# gk_midi_board.net
KiCad netlist of a schematic drawn in EAGLE
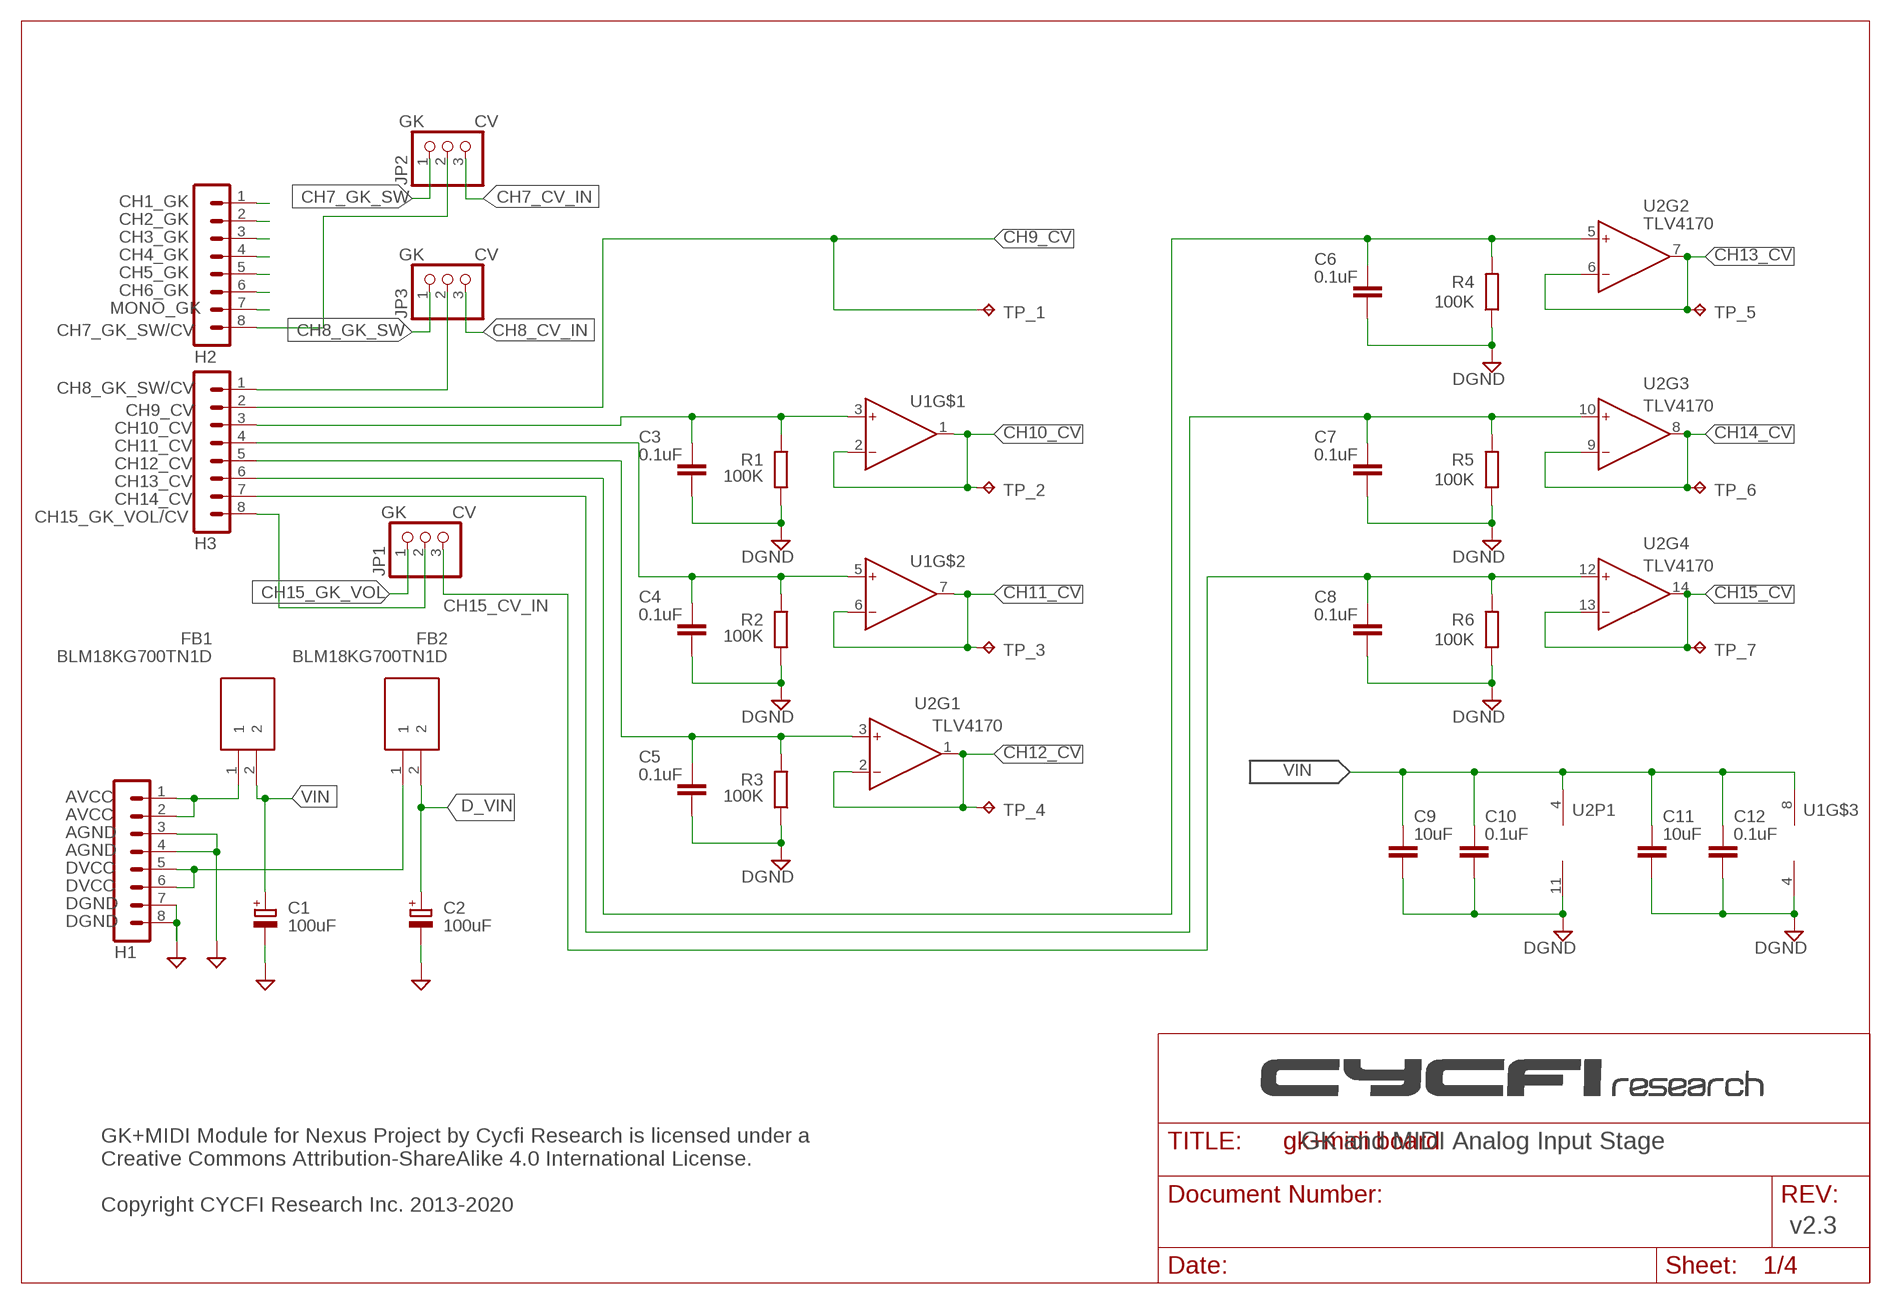
[diagram p0: schematic, sheet 1]
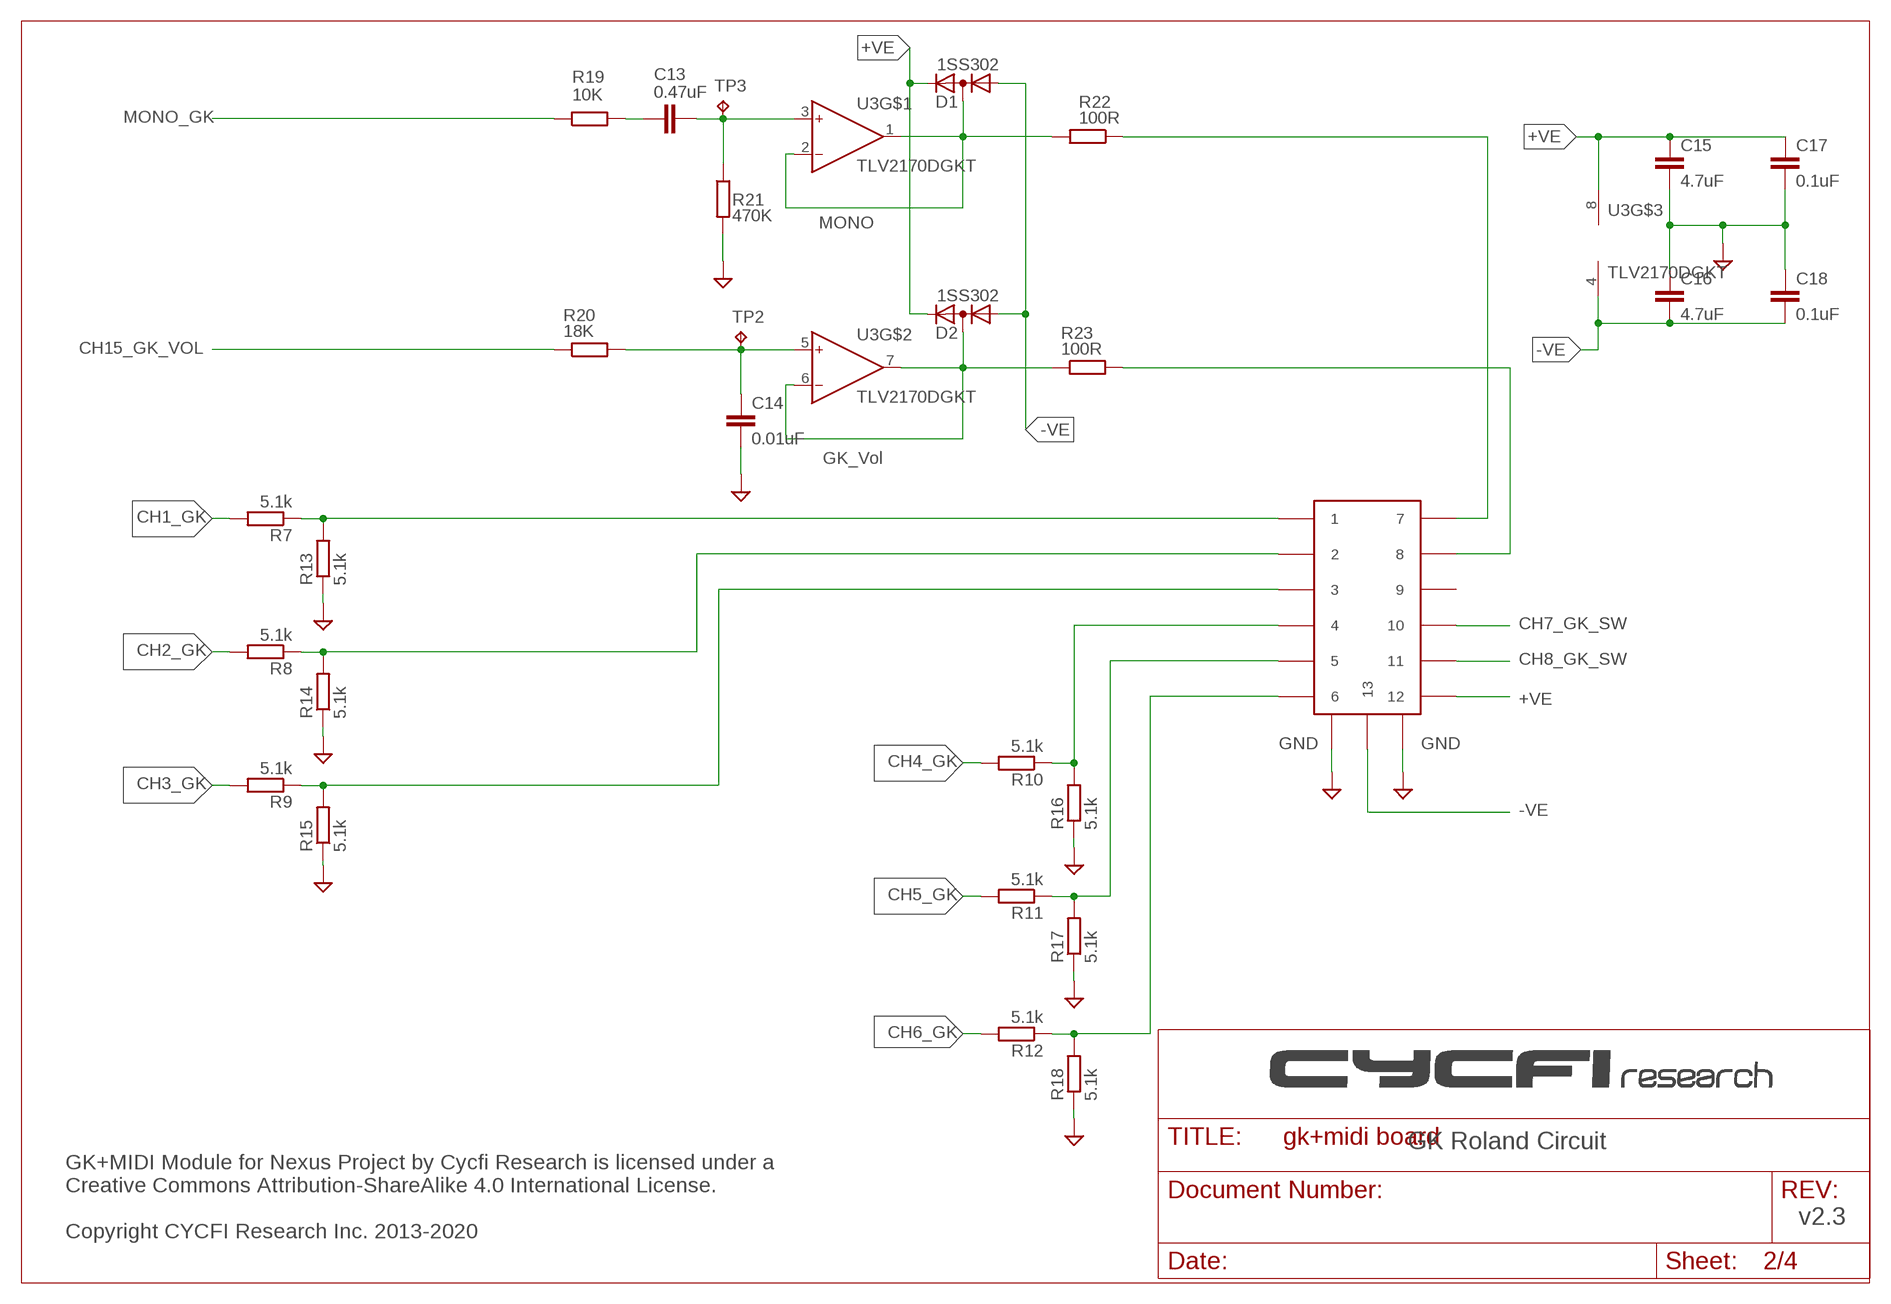
[diagram p1: schematic, sheet 2]
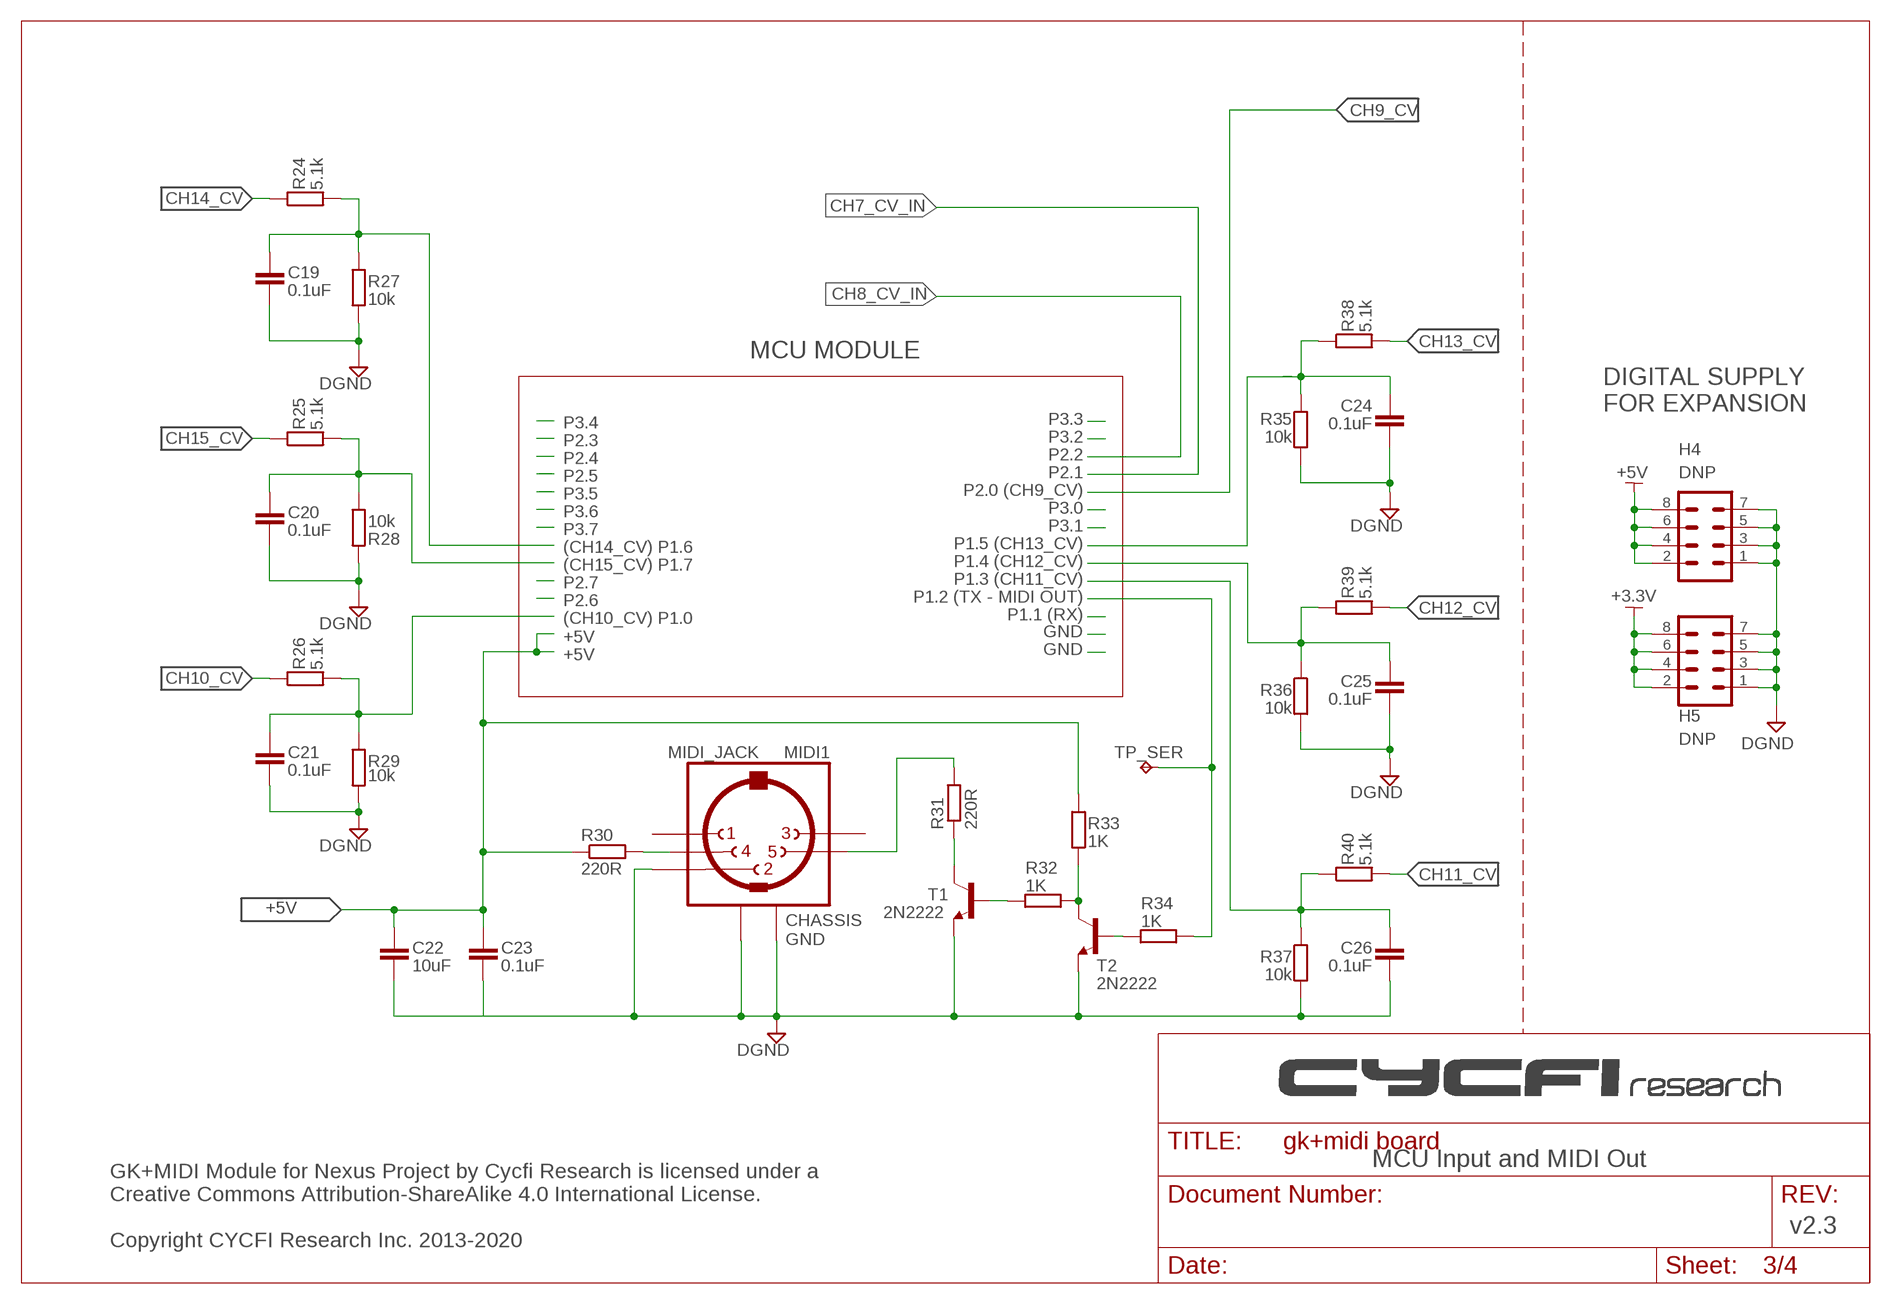
[diagram p2: schematic, sheet 3]
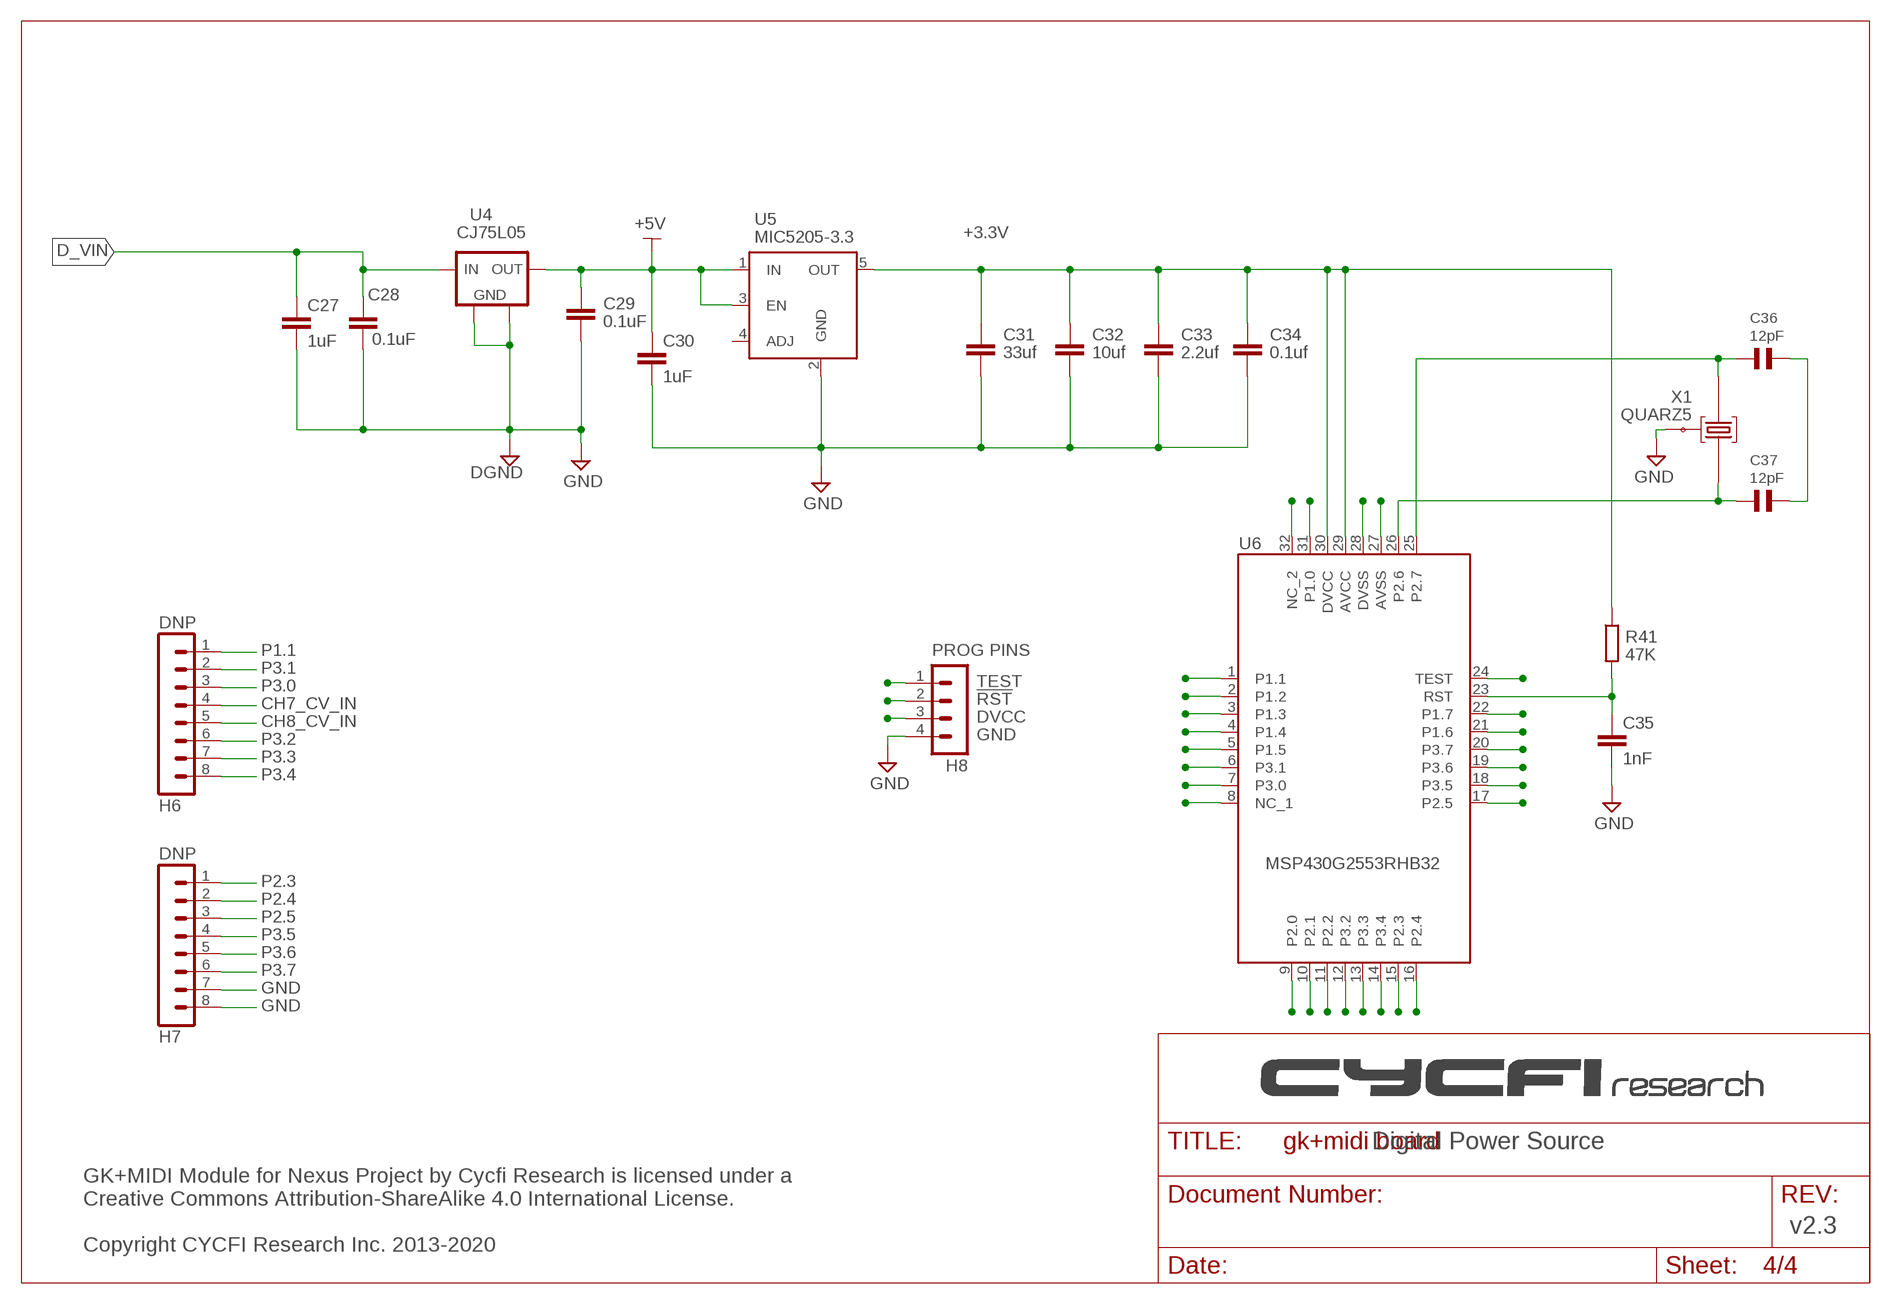
[diagram p3: schematic, sheet 4]

(export (version "E")
  (design (tool "Eeschema 10.0.6"))
  (components
    (comp (ref "13P-CN1")
      (value "13P-MIDI")
      (footprint "eagle-import:13P-MIDI")
      (libsource (lib "eagle-import") (part "13P-MIDI"))
    )
    (comp (ref "C13")
      (value "0.47uF")
      (footprint "eagle-import:C0603")
      (libsource (lib "eagle-import") (part "C-EUC0603"))
    )
    (comp (ref "C14")
      (value "0.01uF")
      (footprint "eagle-import:C0402")
      (libsource (lib "eagle-import") (part "C-EUC0402"))
    )
    (comp (ref "C15")
      (value "4.7uF")
      (footprint "eagle-import:C0603")
      (libsource (lib "eagle-import") (part "C-EUC0603"))
    )
    (comp (ref "C16")
      (value "4.7uF")
      (footprint "eagle-import:C0603")
      (libsource (lib "eagle-import") (part "C-EUC0603"))
    )
    (comp (ref "C17")
      (value "0.1uF")
      (footprint "eagle-import:C0402")
      (libsource (lib "eagle-import") (part "C-EUC0402"))
    )
    (comp (ref "C18")
      (value "0.1uF")
      (footprint "eagle-import:C0402")
      (libsource (lib "eagle-import") (part "C-EUC0402"))
    )
    (comp (ref "D1")
      (value "1SS302")
      (footprint "eagle-import:SC70-3")
      (libsource (lib "eagle-import") (part "1SS302"))
    )
    (comp (ref "D2")
      (value "1SS302")
      (footprint "eagle-import:SC70-3")
      (libsource (lib "eagle-import") (part "1SS302"))
    )
    (comp (ref "R7")
      (value "5.1k")
      (footprint "eagle-import:R0402")
      (libsource (lib "eagle-import") (part "R-EU_R0402"))
    )
    (comp (ref "R8")
      (value "5.1k")
      (footprint "eagle-import:R0402")
      (libsource (lib "eagle-import") (part "R-EU_R0402"))
    )
    (comp (ref "R9")
      (value "5.1k")
      (footprint "eagle-import:R0402")
      (libsource (lib "eagle-import") (part "R-EU_R0402"))
    )
    (comp (ref "R10")
      (value "5.1k")
      (footprint "eagle-import:R0402")
      (libsource (lib "eagle-import") (part "R-EU_R0402"))
    )
    (comp (ref "R11")
      (value "5.1k")
      (footprint "eagle-import:R0402")
      (libsource (lib "eagle-import") (part "R-EU_R0402"))
    )
    (comp (ref "R12")
      (value "5.1k")
      (footprint "eagle-import:R0402")
      (libsource (lib "eagle-import") (part "R-EU_R0402"))
    )
    (comp (ref "R13")
      (value "5.1k")
      (footprint "eagle-import:R0402")
      (libsource (lib "eagle-import") (part "R-EU_R0402"))
    )
    (comp (ref "R14")
      (value "5.1k")
      (footprint "eagle-import:R0402")
      (libsource (lib "eagle-import") (part "R-EU_R0402"))
    )
    (comp (ref "R15")
      (value "5.1k")
      (footprint "eagle-import:R0402")
      (libsource (lib "eagle-import") (part "R-EU_R0402"))
    )
    (comp (ref "R16")
      (value "5.1k")
      (footprint "eagle-import:R0402")
      (libsource (lib "eagle-import") (part "R-EU_R0402"))
    )
    (comp (ref "R17")
      (value "5.1k")
      (footprint "eagle-import:R0402")
      (libsource (lib "eagle-import") (part "R-EU_R0402"))
    )
    (comp (ref "R18")
      (value "5.1k")
      (footprint "eagle-import:R0402")
      (libsource (lib "eagle-import") (part "R-EU_R0402"))
    )
    (comp (ref "R19")
      (value "10K")
      (footprint "eagle-import:R0402")
      (libsource (lib "eagle-import") (part "R-EU_R0402"))
    )
    (comp (ref "R20")
      (value "18K")
      (footprint "eagle-import:R0402")
      (libsource (lib "eagle-import") (part "R-EU_R0402"))
    )
    (comp (ref "R21")
      (value "470K")
      (footprint "eagle-import:R0402")
      (libsource (lib "eagle-import") (part "R-EU_R0402"))
    )
    (comp (ref "R22")
      (value "100R")
      (footprint "eagle-import:R0402")
      (libsource (lib "eagle-import") (part "R-EU_R0402"))
    )
    (comp (ref "R23")
      (value "100R")
      (footprint "eagle-import:R0402")
      (libsource (lib "eagle-import") (part "R-EU_R0402"))
    )
    (comp (ref "TP2")
      (value "TPB1,27")
      (footprint "eagle-import:B1,27")
      (libsource (lib "eagle-import") (part "TPB1,27"))
    )
    (comp (ref "TP3")
      (value "TPB1,27")
      (footprint "eagle-import:B1,27")
      (libsource (lib "eagle-import") (part "TPB1,27"))
    )
    (comp (ref "U3")
      (value "TLV2170DGKT")
      (footprint "eagle-import:MSOP8")
      (libsource (lib "eagle-import") (part "TLV2170DGKT"))
    )
    (comp (ref "C1")
      (value "100uF")
      (footprint "eagle-import:153CLV-0505")
      (libsource (lib "eagle-import") (part "CPOL-EU153CLV-0505"))
    )
    (comp (ref "C2")
      (value "100uF")
      (footprint "eagle-import:153CLV-0505")
      (libsource (lib "eagle-import") (part "CPOL-EU153CLV-0505"))
    )
    (comp (ref "C3")
      (value "0.1uF")
      (footprint "eagle-import:C0603")
      (libsource (lib "eagle-import") (part "C-EUC0603"))
    )
    (comp (ref "C4")
      (value "0.1uF")
      (footprint "eagle-import:C0603")
      (libsource (lib "eagle-import") (part "C-EUC0603"))
    )
    (comp (ref "C5")
      (value "0.1uF")
      (footprint "eagle-import:C0603")
      (libsource (lib "eagle-import") (part "C-EUC0603"))
    )
    (comp (ref "C6")
      (value "0.1uF")
      (footprint "eagle-import:C0603")
      (libsource (lib "eagle-import") (part "C-EUC0603"))
    )
    (comp (ref "C7")
      (value "0.1uF")
      (footprint "eagle-import:C0603")
      (libsource (lib "eagle-import") (part "C-EUC0603"))
    )
    (comp (ref "C8")
      (value "0.1uF")
      (footprint "eagle-import:C0603")
      (libsource (lib "eagle-import") (part "C-EUC0603"))
    )
    (comp (ref "C9")
      (value "10uF")
      (footprint "eagle-import:C0805")
      (libsource (lib "eagle-import") (part "C-EUC0805"))
    )
    (comp (ref "C10")
      (value "0.1uF")
      (footprint "eagle-import:C0603")
      (libsource (lib "eagle-import") (part "C-EUC0603"))
    )
    (comp (ref "C11")
      (value "10uF")
      (footprint "eagle-import:C0805")
      (libsource (lib "eagle-import") (part "C-EUC0805"))
    )
    (comp (ref "C12")
      (value "0.1uF")
      (footprint "eagle-import:C0603")
      (libsource (lib "eagle-import") (part "C-EUC0603"))
    )
    (comp (ref "FB1")
      (value "BLM18KG700TN1D")
      (footprint "eagle-import:BEADC1608X75N")
      (fields (field (name "MOUSER_PART_NUMBER") "81-BLM18KG700TN1D"))
      (libsource (lib "eagle-import") (part "BLM18KG700TN1D"))
    )
    (comp (ref "FB2")
      (value "BLM18KG700TN1D")
      (footprint "eagle-import:BEADC1608X75N")
      (description "BLM18_N1D Series EMI Suppression Filter 70+/-25% at 100MHz 3.5A @85")
      (fields
        (field (name "MOUSER_PART_NUMBER") "81-BLM18KG700TN1D")
        (field (name "HEIGHT") "0.75mm")
        (field (name "MANUFACTURER_NAME") "Murata Electronics")
        (field (name "MANUFACTURER_PART_NUMBER") "BLM18KG700TN1D")
        (field (name "MOUSER_PART_NUMBER_1") "81-BLM18KG700TN1D")
        (field (name "MOUSER_PRICE-STOCK") "https://www.mouser.com/Search/Refine.aspx?Keyword=81-BLM18KG700TN1D")
      )
      (libsource (lib "eagle-import") (part "BLM18KG700TN1D"))
    )
    (comp (ref "H1")
      (value "MA08-1")
      (footprint "eagle-import:MA08-1")
      (libsource (lib "eagle-import") (part "MA08-1"))
    )
    (comp (ref "H2")
      (value "MA08-1")
      (footprint "eagle-import:MA08-1")
      (libsource (lib "eagle-import") (part "MA08-1"))
    )
    (comp (ref "H3")
      (value "MA08-1")
      (footprint "eagle-import:MA08-1")
      (libsource (lib "eagle-import") (part "MA08-1"))
    )
    (comp (ref "JP1")
      (value "PINHD-1X03_2.00")
      (footprint "eagle-import:1X03M")
      (libsource (lib "eagle-import") (part "PINHD-1X03_2.00"))
    )
    (comp (ref "JP2")
      (value "PINHD-1X03_2.00")
      (footprint "eagle-import:1X03M")
      (libsource (lib "eagle-import") (part "PINHD-1X03_2.00"))
    )
    (comp (ref "JP3")
      (value "PINHD-1X03_2.00")
      (footprint "eagle-import:1X03M")
      (libsource (lib "eagle-import") (part "PINHD-1X03_2.00"))
    )
    (comp (ref "R1")
      (value "100K")
      (footprint "eagle-import:R0402")
      (libsource (lib "eagle-import") (part "R-EU_R0402"))
    )
    (comp (ref "R2")
      (value "100K")
      (footprint "eagle-import:R0402")
      (libsource (lib "eagle-import") (part "R-EU_R0402"))
    )
    (comp (ref "R3")
      (value "100K")
      (footprint "eagle-import:R0402")
      (libsource (lib "eagle-import") (part "R-EU_R0402"))
    )
    (comp (ref "R4")
      (value "100K")
      (footprint "eagle-import:R0402")
      (libsource (lib "eagle-import") (part "R-EU_R0402"))
    )
    (comp (ref "R5")
      (value "100K")
      (footprint "eagle-import:R0402")
      (libsource (lib "eagle-import") (part "R-EU_R0402"))
    )
    (comp (ref "R6")
      (value "100K")
      (footprint "eagle-import:R0402")
      (libsource (lib "eagle-import") (part "R-EU_R0402"))
    )
    (comp (ref "TP_1")
      (value "TPB1,27")
      (footprint "eagle-import:B1,27")
      (libsource (lib "eagle-import") (part "TPB1,27"))
    )
    (comp (ref "TP_2")
      (value "TPB1,27")
      (footprint "eagle-import:B1,27")
      (libsource (lib "eagle-import") (part "TPB1,27"))
    )
    (comp (ref "TP_3")
      (value "TPB1,27")
      (footprint "eagle-import:B1,27")
      (libsource (lib "eagle-import") (part "TPB1,27"))
    )
    (comp (ref "TP_4")
      (value "TPB1,27")
      (footprint "eagle-import:B1,27")
      (libsource (lib "eagle-import") (part "TPB1,27"))
    )
    (comp (ref "TP_5")
      (value "TPB1,27")
      (footprint "eagle-import:B1,27")
      (libsource (lib "eagle-import") (part "TPB1,27"))
    )
    (comp (ref "TP_6")
      (value "TPB1,27")
      (footprint "eagle-import:B1,27")
      (libsource (lib "eagle-import") (part "TPB1,27"))
    )
    (comp (ref "TP_7")
      (value "TPB1,27")
      (footprint "eagle-import:B1,27")
      (libsource (lib "eagle-import") (part "TPB1,27"))
    )
    (comp (ref "U1")
      (value "TLV2170DGKT")
      (footprint "eagle-import:MSOP8")
      (libsource (lib "eagle-import") (part "TLV2170DGKT"))
    )
    (comp (ref "U2")
      (value "LMV324")
      (footprint "eagle-import:SSOP-14")
      (libsource (lib "eagle-import") (part "LMV324"))
    )
    (comp (ref "C27")
      (value "1uF")
      (footprint "eagle-import:C0402")
      (libsource (lib "eagle-import") (part "C-EUC0402"))
    )
    (comp (ref "C28")
      (value "0.1uF")
      (footprint "eagle-import:C0603")
      (libsource (lib "eagle-import") (part "C-EUC0603"))
    )
    (comp (ref "C29")
      (value "0.1uF")
      (footprint "eagle-import:C0603")
      (libsource (lib "eagle-import") (part "C-EUC0603"))
    )
    (comp (ref "C30")
      (value "1uF")
      (footprint "eagle-import:C0402")
      (libsource (lib "eagle-import") (part "C-EUC0402"))
    )
    (comp (ref "C31")
      (value "33uf")
      (footprint "eagle-import:C0805")
      (libsource (lib "eagle-import") (part "C-EUC0805"))
    )
    (comp (ref "C32")
      (value "10uf")
      (footprint "eagle-import:C0805")
      (libsource (lib "eagle-import") (part "C-EUC0805"))
    )
    (comp (ref "C33")
      (value "2.2uf")
      (footprint "eagle-import:C0805")
      (libsource (lib "eagle-import") (part "C-EUC0805"))
    )
    (comp (ref "C34")
      (value "0.1uf")
      (footprint "eagle-import:C0603")
      (libsource (lib "eagle-import") (part "C-EUC0603"))
    )
    (comp (ref "C35")
      (value "1nF")
      (footprint "eagle-import:C0402")
      (libsource (lib "eagle-import") (part "C-EUC0402"))
    )
    (comp (ref "C36")
      (value "12pF")
      (footprint "eagle-import:0603")
      (libsource (lib "eagle-import") (part "C_SMD0603"))
    )
    (comp (ref "C37")
      (value "12pF")
      (footprint "eagle-import:0603")
      (libsource (lib "eagle-import") (part "C_SMD0603"))
    )
    (comp (ref "H6")
      (value "DNP")
      (footprint "eagle-import:MA08-1")
      (libsource (lib "eagle-import") (part "MA08-1"))
    )
    (comp (ref "H7")
      (value "DNP")
      (footprint "eagle-import:MA08-1")
      (libsource (lib "eagle-import") (part "MA08-1"))
    )
    (comp (ref "H8")
      (value "MA04-1")
      (footprint "eagle-import:MA04-1")
      (libsource (lib "eagle-import") (part "MA04-1"))
    )
    (comp (ref "R41")
      (value "47K")
      (footprint "eagle-import:R0402")
      (libsource (lib "eagle-import") (part "R-EU_R0402"))
    )
    (comp (ref "U4")
      (value "L78LXX")
      (footprint "eagle-import:SOT89")
      (libsource (lib "eagle-import") (part "L78LXX"))
    )
    (comp (ref "U5")
      (value "MIC5205-3.3")
      (footprint "eagle-import:SOT23-5")
      (fields (field (name "MF") "ALTERA CORPORATION") (field (name "MPN") "MIC5219BM5 TR"))
      (libsource (lib "eagle-import") (part "MIC5219BM5"))
    )
    (comp (ref "U6")
      (value "MSP430G2553RHB32")
      (footprint "eagle-import:QFN32")
      (libsource (lib "eagle-import") (part "MSP430G2553RHB32"))
    )
    (comp (ref "X1")
      (value "QUARZ5")
      (footprint "eagle-import:QUARZ5")
      (libsource (lib "eagle-import") (part "QUARZ5"))
    )
    (comp (ref "C19")
      (value "0.1uF")
      (footprint "eagle-import:C0603")
      (libsource (lib "eagle-import") (part "C-EUC0603"))
    )
    (comp (ref "C20")
      (value "0.1uF")
      (footprint "eagle-import:C0603")
      (libsource (lib "eagle-import") (part "C-EUC0603"))
    )
    (comp (ref "C21")
      (value "0.1uF")
      (footprint "eagle-import:C0603")
      (libsource (lib "eagle-import") (part "C-EUC0603"))
    )
    (comp (ref "C22")
      (value "10uF")
      (footprint "eagle-import:C0805")
      (libsource (lib "eagle-import") (part "C-EUC0805"))
    )
    (comp (ref "C23")
      (value "0.1uF")
      (footprint "eagle-import:C0603")
      (libsource (lib "eagle-import") (part "C-EUC0603"))
    )
    (comp (ref "C24")
      (value "0.1uF")
      (footprint "eagle-import:C0603")
      (libsource (lib "eagle-import") (part "C-EUC0603"))
    )
    (comp (ref "C25")
      (value "0.1uF")
      (footprint "eagle-import:C0603")
      (libsource (lib "eagle-import") (part "C-EUC0603"))
    )
    (comp (ref "C26")
      (value "0.1uF")
      (footprint "eagle-import:C0603")
      (libsource (lib "eagle-import") (part "C-EUC0603"))
    )
    (comp (ref "H4")
      (value "DNP")
      (footprint "eagle-import:MA04-2")
      (libsource (lib "eagle-import") (part "MA04-2"))
    )
    (comp (ref "H5")
      (value "DNP")
      (footprint "eagle-import:MA04-2")
      (libsource (lib "eagle-import") (part "MA04-2"))
    )
    (comp (ref "MIDI1")
      (value "MIDI_JACK")
      (footprint "eagle-import:MIDI_JACK")
      (libsource (lib "eagle-import") (part "MIDI_JACK"))
    )
    (comp (ref "R24")
      (value "5.1k")
      (footprint "eagle-import:R0402")
      (libsource (lib "eagle-import") (part "R-EU_R0402"))
    )
    (comp (ref "R25")
      (value "5.1k")
      (footprint "eagle-import:R0402")
      (libsource (lib "eagle-import") (part "R-EU_R0402"))
    )
    (comp (ref "R26")
      (value "5.1k")
      (footprint "eagle-import:R0402")
      (libsource (lib "eagle-import") (part "R-EU_R0402"))
    )
    (comp (ref "R27")
      (value "10k")
      (footprint "eagle-import:R0402")
      (libsource (lib "eagle-import") (part "R-EU_R0402"))
    )
    (comp (ref "R28")
      (value "10k")
      (footprint "eagle-import:R0402")
      (libsource (lib "eagle-import") (part "R-EU_R0402"))
    )
    (comp (ref "R29")
      (value "10k")
      (footprint "eagle-import:R0402")
      (libsource (lib "eagle-import") (part "R-EU_R0402"))
    )
    (comp (ref "R30")
      (value "220R")
      (footprint "eagle-import:R0603")
      (libsource (lib "eagle-import") (part "R-EU_R0603"))
    )
    (comp (ref "R31")
      (value "220R")
      (footprint "eagle-import:R0603")
      (libsource (lib "eagle-import") (part "R-EU_R0603"))
    )
    (comp (ref "R32")
      (value "1K")
      (footprint "eagle-import:R0402")
      (libsource (lib "eagle-import") (part "R-EU_R0402"))
    )
    (comp (ref "R33")
      (value "1K")
      (footprint "eagle-import:R0402")
      (libsource (lib "eagle-import") (part "R-EU_R0402"))
    )
    (comp (ref "R34")
      (value "1K")
      (footprint "eagle-import:R0402")
      (libsource (lib "eagle-import") (part "R-EU_R0402"))
    )
    (comp (ref "R35")
      (value "10k")
      (footprint "eagle-import:R0402")
      (libsource (lib "eagle-import") (part "R-EU_R0402"))
    )
    (comp (ref "R36")
      (value "10k")
      (footprint "eagle-import:R0402")
      (libsource (lib "eagle-import") (part "R-EU_R0402"))
    )
    (comp (ref "R37")
      (value "10k")
      (footprint "eagle-import:R0402")
      (libsource (lib "eagle-import") (part "R-EU_R0402"))
    )
    (comp (ref "R38")
      (value "5.1k")
      (footprint "eagle-import:R0402")
      (libsource (lib "eagle-import") (part "R-EU_R0402"))
    )
    (comp (ref "R39")
      (value "5.1k")
      (footprint "eagle-import:R0402")
      (libsource (lib "eagle-import") (part "R-EU_R0402"))
    )
    (comp (ref "R40")
      (value "5.1k")
      (footprint "eagle-import:R0402")
      (libsource (lib "eagle-import") (part "R-EU_R0402"))
    )
    (comp (ref "T1")
      (value "2N2222")
      (footprint "eagle-import:SOT23-3")
      (libsource (lib "eagle-import") (part "TRAN-MMBT2222A"))
    )
    (comp (ref "T2")
      (value "2N2222")
      (footprint "eagle-import:SOT23-3")
      (libsource (lib "eagle-import") (part "TRAN-MMBT2222A"))
    )
    (comp (ref "TP_SER")
      (value "TPB1,27")
      (footprint "eagle-import:B1,27")
      (libsource (lib "eagle-import") (part "TPB1,27"))
    )
  )
  (nets
    (net (code "1") (name "+3.3V") (class "Default")
      (node (ref "C31") (pin "1") (pinfunction "1_1") (pintype "passive"))
      (node (ref "C32") (pin "1") (pinfunction "1_1") (pintype "passive"))
      (node (ref "C33") (pin "1") (pinfunction "1_1") (pintype "passive"))
      (node (ref "C34") (pin "1") (pinfunction "1_1") (pintype "passive"))
      (node (ref "H5") (pin "2") (pinfunction "2_2") (pintype "passive"))
      (node (ref "H5") (pin "4") (pinfunction "4_4") (pintype "passive"))
      (node (ref "H5") (pin "6") (pinfunction "6_6") (pintype "passive"))
      (node (ref "H5") (pin "8") (pinfunction "8_8") (pintype "passive"))
      (node (ref "H8") (pin "3") (pinfunction "3_3") (pintype "passive"))
      (node (ref "R41") (pin "1") (pinfunction "1_1") (pintype "passive"))
      (node (ref "U5") (pin "5") (pinfunction "OUT_5") (pintype "output"))
      (node (ref "U6") (pin "29") (pinfunction "AVCC_29") (pintype "bidirectional"))
      (node (ref "U6") (pin "30") (pinfunction "DVCC_30") (pintype "bidirectional"))
    )
    (net (code "2") (name "+5V") (class "Default")
      (node (ref "C22") (pin "1") (pinfunction "1_1") (pintype "passive"))
      (node (ref "C23") (pin "1") (pinfunction "1_1") (pintype "passive"))
      (node (ref "C29") (pin "1") (pinfunction "1_1") (pintype "passive"))
      (node (ref "C30") (pin "1") (pinfunction "1_1") (pintype "passive"))
      (node (ref "H4") (pin "2") (pinfunction "2_2") (pintype "passive"))
      (node (ref "H4") (pin "4") (pinfunction "4_4") (pintype "passive"))
      (node (ref "H4") (pin "6") (pinfunction "6_6") (pintype "passive"))
      (node (ref "H4") (pin "8") (pinfunction "8_8") (pintype "passive"))
      (node (ref "R30") (pin "1") (pinfunction "1_1") (pintype "passive"))
      (node (ref "R33") (pin "2") (pinfunction "2_2") (pintype "passive"))
      (node (ref "U4") (pin "1") (pinfunction "IN_1") (pintype "input"))
      (node (ref "U5") (pin "1") (pinfunction "IN_1") (pintype "input"))
      (node (ref "U5") (pin "3") (pinfunction "EN_3") (pintype "input"))
    )
    (net (code "3") (name "+VE") (class "Default")
      (node (ref "13P-CN1") (pin "12") (pinfunction "12_12") (pintype "bidirectional"))
      (node (ref "C15") (pin "1") (pinfunction "1_1") (pintype "passive"))
      (node (ref "C17") (pin "1") (pinfunction "1_1") (pintype "passive"))
      (node (ref "D1") (pin "2") (pinfunction "K_2") (pintype "passive"))
      (node (ref "D2") (pin "2") (pinfunction "K_2") (pintype "passive"))
      (node (ref "U3") (pin "8") (pinfunction "V+_8") (pintype "power_in"))
    )
    (net (code "4") (name "-VE") (class "Default")
      (node (ref "13P-CN1") (pin "13") (pinfunction "13_13") (pintype "bidirectional"))
      (node (ref "C16") (pin "2") (pinfunction "2_2") (pintype "passive"))
      (node (ref "C18") (pin "2") (pinfunction "2_2") (pintype "passive"))
      (node (ref "D1") (pin "1") (pinfunction "A_1") (pintype "passive"))
      (node (ref "D2") (pin "1") (pinfunction "A_1") (pintype "passive"))
      (node (ref "U3") (pin "4") (pinfunction "V-_4") (pintype "power_in"))
    )
    (net (code "5") (name "AVCC") (class "Default")
      (node (ref "FB1") (pin "1") (pinfunction "1_1") (pintype "bidirectional"))
      (node (ref "H1") (pin "1") (pinfunction "1_1") (pintype "passive"))
      (node (ref "H1") (pin "2") (pinfunction "2_2") (pintype "passive"))
    )
    (net (code "6") (name "CH1_GK") (class "Default")
      (node (ref "H2") (pin "1") (pinfunction "1_1") (pintype "passive"))
      (node (ref "R7") (pin "2") (pinfunction "2_2") (pintype "passive"))
    )
    (net (code "7") (name "CH2_GK") (class "Default")
      (node (ref "H2") (pin "2") (pinfunction "2_2") (pintype "passive"))
      (node (ref "R8") (pin "2") (pinfunction "2_2") (pintype "passive"))
    )
    (net (code "8") (name "CH3_GK") (class "Default")
      (node (ref "H2") (pin "3") (pinfunction "3_3") (pintype "passive"))
      (node (ref "R9") (pin "2") (pinfunction "2_2") (pintype "passive"))
    )
    (net (code "9") (name "CH4_GK") (class "Default")
      (node (ref "H2") (pin "4") (pinfunction "4_4") (pintype "passive"))
      (node (ref "R10") (pin "2") (pinfunction "2_2") (pintype "passive"))
    )
    (net (code "10") (name "CH5_GK") (class "Default")
      (node (ref "H2") (pin "5") (pinfunction "5_5") (pintype "passive"))
      (node (ref "R11") (pin "2") (pinfunction "2_2") (pintype "passive"))
    )
    (net (code "11") (name "CH6_GK") (class "Default")
      (node (ref "H2") (pin "6") (pinfunction "6_6") (pintype "passive"))
      (node (ref "R12") (pin "2") (pinfunction "2_2") (pintype "passive"))
    )
    (net (code "12") (name "CH7_CV_IN") (class "Default")
      (node (ref "H6") (pin "4") (pinfunction "4_4") (pintype "passive"))
      (node (ref "JP2") (pin "3") (pinfunction "3_3") (pintype "passive"))
      (node (ref "U6") (pin "10") (pinfunction "P2.1_10") (pintype "bidirectional"))
    )
    (net (code "13") (name "CH7_GK_SW") (class "Default")
      (node (ref "13P-CN1") (pin "10") (pinfunction "10_10") (pintype "bidirectional"))
      (node (ref "JP2") (pin "1") (pinfunction "1_1") (pintype "passive"))
    )
    (net (code "14") (name "CH8_CV_IN") (class "Default")
      (node (ref "H6") (pin "5") (pinfunction "5_5") (pintype "passive"))
      (node (ref "JP3") (pin "3") (pinfunction "3_3") (pintype "passive"))
      (node (ref "U6") (pin "11") (pinfunction "P2.2_11") (pintype "bidirectional"))
    )
    (net (code "15") (name "CH8_GK_SW") (class "Default")
      (node (ref "13P-CN1") (pin "11") (pinfunction "11_11") (pintype "bidirectional"))
      (node (ref "JP3") (pin "1") (pinfunction "1_1") (pintype "passive"))
    )
    (net (code "16") (name "CH9_CV") (class "Default")
      (node (ref "H3") (pin "2") (pinfunction "2_2") (pintype "passive"))
      (node (ref "TP_1") (pin "TP") (pinfunction "TP_TP") (pintype "input"))
      (node (ref "U6") (pin "9") (pinfunction "P2.0_9") (pintype "bidirectional"))
    )
    (net (code "17") (name "CH10_CV") (class "Default")
      (node (ref "R26") (pin "1") (pinfunction "1_1") (pintype "passive"))
      (node (ref "TP_2") (pin "TP") (pinfunction "TP_TP") (pintype "input"))
      (node (ref "U1") (pin "1") (pinfunction "OUT_1") (pintype "output"))
      (node (ref "U1") (pin "2") (pinfunction "IN-_2") (pintype "input"))
    )
    (net (code "18") (name "CH11_CV") (class "Default")
      (node (ref "R40") (pin "2") (pinfunction "2_2") (pintype "passive"))
      (node (ref "TP_3") (pin "TP") (pinfunction "TP_TP") (pintype "input"))
      (node (ref "U1") (pin "6") (pinfunction "IN-_6") (pintype "input"))
      (node (ref "U1") (pin "7") (pinfunction "OUT_7") (pintype "output"))
    )
    (net (code "19") (name "CH12_CV") (class "Default")
      (node (ref "R39") (pin "2") (pinfunction "2_2") (pintype "passive"))
      (node (ref "TP_4") (pin "TP") (pinfunction "TP_TP") (pintype "input"))
      (node (ref "U2") (pin "1") (pinfunction "OUT_1") (pintype "output"))
      (node (ref "U2") (pin "2") (pinfunction "IN-_2") (pintype "input"))
    )
    (net (code "20") (name "CH13_CV") (class "Default")
      (node (ref "R38") (pin "2") (pinfunction "2_2") (pintype "passive"))
      (node (ref "TP_5") (pin "TP") (pinfunction "TP_TP") (pintype "input"))
      (node (ref "U2") (pin "6") (pinfunction "IN-_6") (pintype "input"))
      (node (ref "U2") (pin "7") (pinfunction "OUT_7") (pintype "output"))
    )
    (net (code "21") (name "CH14_CV") (class "Default")
      (node (ref "R24") (pin "1") (pinfunction "1_1") (pintype "passive"))
      (node (ref "TP_6") (pin "TP") (pinfunction "TP_TP") (pintype "input"))
      (node (ref "U2") (pin "8") (pinfunction "OUT_8") (pintype "output"))
      (node (ref "U2") (pin "9") (pinfunction "IN-_9") (pintype "input"))
    )
    (net (code "22") (name "CH15_CV") (class "Default")
      (node (ref "R25") (pin "1") (pinfunction "1_1") (pintype "passive"))
      (node (ref "TP_7") (pin "TP") (pinfunction "TP_TP") (pintype "input"))
      (node (ref "U2") (pin "13") (pinfunction "IN-_13") (pintype "input"))
      (node (ref "U2") (pin "14") (pinfunction "OUT_14") (pintype "output"))
    )
    (net (code "23") (name "CH15_CV_IN") (class "Default")
      (node (ref "C8") (pin "1") (pinfunction "1_1") (pintype "passive"))
      (node (ref "JP1") (pin "3") (pinfunction "3_3") (pintype "passive"))
      (node (ref "R6") (pin "2") (pinfunction "2_2") (pintype "passive"))
      (node (ref "U2") (pin "12") (pinfunction "IN+_12") (pintype "input"))
    )
    (net (code "24") (name "CH15_GK_VOL") (class "Default")
      (node (ref "JP1") (pin "1") (pinfunction "1_1") (pintype "passive"))
      (node (ref "R20") (pin "1") (pinfunction "1_1") (pintype "passive"))
    )
    (net (code "25") (name "DVCC") (class "Default")
      (node (ref "FB2") (pin "1") (pinfunction "1_1") (pintype "bidirectional"))
      (node (ref "H1") (pin "5") (pinfunction "5_5") (pintype "passive"))
      (node (ref "H1") (pin "6") (pinfunction "6_6") (pintype "passive"))
    )
    (net (code "26") (name "D_VIN") (class "Default")
      (node (ref "C2") (pin "+") (pinfunction "+_+") (pintype "passive"))
      (node (ref "C27") (pin "1") (pinfunction "1_1") (pintype "passive"))
      (node (ref "C28") (pin "1") (pinfunction "1_1") (pintype "passive"))
      (node (ref "FB2") (pin "2") (pinfunction "2_2") (pintype "bidirectional"))
      (node (ref "U4") (pin "3") (pinfunction "OUT_3") (pintype "passive"))
    )
    (net (code "27") (name "GND") (class "Default")
      (node (ref "13P-CN1") (pin "P$14") (pinfunction "14_P$14") (pintype "bidirectional"))
      (node (ref "13P-CN1") (pin "P$15") (pinfunction "15_P$15") (pintype "bidirectional"))
      (node (ref "C1") (pin "-") (pinfunction "-_-") (pintype "passive"))
      (node (ref "C10") (pin "2") (pinfunction "2_2") (pintype "passive"))
      (node (ref "C11") (pin "2") (pinfunction "2_2") (pintype "passive"))
      (node (ref "C12") (pin "2") (pinfunction "2_2") (pintype "passive"))
      (node (ref "C14") (pin "2") (pinfunction "2_2") (pintype "passive"))
      (node (ref "C15") (pin "2") (pinfunction "2_2") (pintype "passive"))
      (node (ref "C16") (pin "1") (pinfunction "1_1") (pintype "passive"))
      (node (ref "C17") (pin "2") (pinfunction "2_2") (pintype "passive"))
      (node (ref "C18") (pin "1") (pinfunction "1_1") (pintype "passive"))
      (node (ref "C19") (pin "2") (pinfunction "2_2") (pintype "passive"))
      (node (ref "C2") (pin "-") (pinfunction "-_-") (pintype "passive"))
      (node (ref "C20") (pin "2") (pinfunction "2_2") (pintype "passive"))
      (node (ref "C21") (pin "2") (pinfunction "2_2") (pintype "passive"))
      (node (ref "C22") (pin "2") (pinfunction "2_2") (pintype "passive"))
      (node (ref "C23") (pin "2") (pinfunction "2_2") (pintype "passive"))
      (node (ref "C24") (pin "2") (pinfunction "2_2") (pintype "passive"))
      (node (ref "C25") (pin "2") (pinfunction "2_2") (pintype "passive"))
      (node (ref "C26") (pin "2") (pinfunction "2_2") (pintype "passive"))
      (node (ref "C27") (pin "2") (pinfunction "2_2") (pintype "passive"))
      (node (ref "C28") (pin "2") (pinfunction "2_2") (pintype "passive"))
      (node (ref "C29") (pin "2") (pinfunction "2_2") (pintype "passive"))
      (node (ref "C3") (pin "2") (pinfunction "2_2") (pintype "passive"))
      (node (ref "C30") (pin "2") (pinfunction "2_2") (pintype "passive"))
      (node (ref "C31") (pin "2") (pinfunction "2_2") (pintype "passive"))
      (node (ref "C32") (pin "2") (pinfunction "2_2") (pintype "passive"))
      (node (ref "C33") (pin "2") (pinfunction "2_2") (pintype "passive"))
      (node (ref "C34") (pin "2") (pinfunction "2_2") (pintype "passive"))
      (node (ref "C35") (pin "2") (pinfunction "2_2") (pintype "passive"))
      (node (ref "C36") (pin "1") (pinfunction "1_1") (pintype "passive"))
      (node (ref "C37") (pin "1") (pinfunction "1_1") (pintype "passive"))
      (node (ref "C4") (pin "2") (pinfunction "2_2") (pintype "passive"))
      (node (ref "C5") (pin "2") (pinfunction "2_2") (pintype "passive"))
      (node (ref "C6") (pin "2") (pinfunction "2_2") (pintype "passive"))
      (node (ref "C7") (pin "2") (pinfunction "2_2") (pintype "passive"))
      (node (ref "C8") (pin "2") (pinfunction "2_2") (pintype "passive"))
      (node (ref "C9") (pin "2") (pinfunction "2_2") (pintype "passive"))
      (node (ref "H1") (pin "3") (pinfunction "3_3") (pintype "passive"))
      (node (ref "H1") (pin "4") (pinfunction "4_4") (pintype "passive"))
      (node (ref "H1") (pin "7") (pinfunction "7_7") (pintype "passive"))
      (node (ref "H1") (pin "8") (pinfunction "8_8") (pintype "passive"))
      (node (ref "H4") (pin "1") (pinfunction "1_1") (pintype "passive"))
      (node (ref "H4") (pin "3") (pinfunction "3_3") (pintype "passive"))
      (node (ref "H4") (pin "5") (pinfunction "5_5") (pintype "passive"))
      (node (ref "H4") (pin "7") (pinfunction "7_7") (pintype "passive"))
      (node (ref "H5") (pin "1") (pinfunction "1_1") (pintype "passive"))
      (node (ref "H5") (pin "3") (pinfunction "3_3") (pintype "passive"))
      (node (ref "H5") (pin "5") (pinfunction "5_5") (pintype "passive"))
      (node (ref "H5") (pin "7") (pinfunction "7_7") (pintype "passive"))
      (node (ref "H7") (pin "7") (pinfunction "7_7") (pintype "passive"))
      (node (ref "H7") (pin "8") (pinfunction "8_8") (pintype "passive"))
      (node (ref "H8") (pin "4") (pinfunction "4_4") (pintype "passive"))
      (node (ref "MIDI1") (pin "2") (pinfunction "2_2") (pintype "passive"))
      (node (ref "MIDI1") (pin "G1") (pinfunction "G1_G1") (pintype "bidirectional"))
      (node (ref "MIDI1") (pin "G2") (pinfunction "G2_G2") (pintype "bidirectional"))
      (node (ref "R1") (pin "1") (pinfunction "1_1") (pintype "passive"))
      (node (ref "R13") (pin "1") (pinfunction "1_1") (pintype "passive"))
      (node (ref "R14") (pin "1") (pinfunction "1_1") (pintype "passive"))
      (node (ref "R15") (pin "1") (pinfunction "1_1") (pintype "passive"))
      (node (ref "R16") (pin "1") (pinfunction "1_1") (pintype "passive"))
      (node (ref "R17") (pin "1") (pinfunction "1_1") (pintype "passive"))
      (node (ref "R18") (pin "1") (pinfunction "1_1") (pintype "passive"))
      (node (ref "R2") (pin "1") (pinfunction "1_1") (pintype "passive"))
      (node (ref "R21") (pin "2") (pinfunction "2_2") (pintype "passive"))
      (node (ref "R27") (pin "2") (pinfunction "2_2") (pintype "passive"))
      (node (ref "R28") (pin "2") (pinfunction "2_2") (pintype "passive"))
      (node (ref "R29") (pin "2") (pinfunction "2_2") (pintype "passive"))
      (node (ref "R3") (pin "1") (pinfunction "1_1") (pintype "passive"))
      (node (ref "R35") (pin "2") (pinfunction "2_2") (pintype "passive"))
      (node (ref "R36") (pin "2") (pinfunction "2_2") (pintype "passive"))
      (node (ref "R37") (pin "2") (pinfunction "2_2") (pintype "passive"))
      (node (ref "R4") (pin "1") (pinfunction "1_1") (pintype "passive"))
      (node (ref "R5") (pin "1") (pinfunction "1_1") (pintype "passive"))
      (node (ref "R6") (pin "1") (pinfunction "1_1") (pintype "passive"))
      (node (ref "T1") (pin "2") (pinfunction "E_2") (pintype "passive"))
      (node (ref "T2") (pin "2") (pinfunction "E_2") (pintype "passive"))
      (node (ref "U1") (pin "4") (pinfunction "V-_4") (pintype "power_in"))
      (node (ref "U2") (pin "11") (pinfunction "V-_11") (pintype "power_in"))
      (node (ref "U4") (pin "2") (pinfunction "GND_2") (pintype "input"))
      (node (ref "U4") (pin "2@1") (pinfunction "GND1_2@1") (pintype "input"))
      (node (ref "U5") (pin "2") (pinfunction "GND_2") (pintype "power_in"))
      (node (ref "U6") (pin "27") (pinfunction "AVSS_27") (pintype "bidirectional"))
      (node (ref "U6") (pin "28") (pinfunction "DVSS_28") (pintype "power_in"))
      (node (ref "X1") (pin "GND@0") (pinfunction "0_GND@0") (pintype "passive"))
    )
    (net (code "28") (name "MONO_GK") (class "Default")
      (node (ref "H2") (pin "7") (pinfunction "7_7") (pintype "passive"))
      (node (ref "R19") (pin "1") (pinfunction "1_1") (pintype "passive"))
    )
    (net (code "29") (name "Net-(13P-CN1-Pad1)") (class "Default")
      (node (ref "13P-CN1") (pin "1") (pinfunction "1_1") (pintype "bidirectional"))
      (node (ref "R13") (pin "2") (pinfunction "2_2") (pintype "passive"))
      (node (ref "R7") (pin "1") (pinfunction "1_1") (pintype "passive"))
    )
    (net (code "30") (name "Net-(13P-CN1-Pad2)") (class "Default")
      (node (ref "13P-CN1") (pin "2") (pinfunction "2_2") (pintype "bidirectional"))
      (node (ref "R14") (pin "2") (pinfunction "2_2") (pintype "passive"))
      (node (ref "R8") (pin "1") (pinfunction "1_1") (pintype "passive"))
    )
    (net (code "31") (name "Net-(13P-CN1-Pad3)") (class "Default")
      (node (ref "13P-CN1") (pin "3") (pinfunction "3_3") (pintype "bidirectional"))
      (node (ref "R15") (pin "2") (pinfunction "2_2") (pintype "passive"))
      (node (ref "R9") (pin "1") (pinfunction "1_1") (pintype "passive"))
    )
    (net (code "32") (name "Net-(13P-CN1-Pad4)") (class "Default")
      (node (ref "13P-CN1") (pin "4") (pinfunction "4_4") (pintype "bidirectional"))
      (node (ref "R10") (pin "1") (pinfunction "1_1") (pintype "passive"))
      (node (ref "R16") (pin "2") (pinfunction "2_2") (pintype "passive"))
    )
    (net (code "33") (name "Net-(13P-CN1-Pad5)") (class "Default")
      (node (ref "13P-CN1") (pin "5") (pinfunction "5_5") (pintype "bidirectional"))
      (node (ref "R11") (pin "1") (pinfunction "1_1") (pintype "passive"))
      (node (ref "R17") (pin "2") (pinfunction "2_2") (pintype "passive"))
    )
    (net (code "34") (name "Net-(13P-CN1-Pad6)") (class "Default")
      (node (ref "13P-CN1") (pin "6") (pinfunction "6_6") (pintype "bidirectional"))
      (node (ref "R12") (pin "1") (pinfunction "1_1") (pintype "passive"))
      (node (ref "R18") (pin "2") (pinfunction "2_2") (pintype "passive"))
    )
    (net (code "35") (name "Net-(13P-CN1-Pad7)") (class "Default")
      (node (ref "13P-CN1") (pin "7") (pinfunction "7_7") (pintype "bidirectional"))
      (node (ref "R22") (pin "1") (pinfunction "1_1") (pintype "passive"))
    )
    (net (code "36") (name "Net-(13P-CN1-Pad8)") (class "Default")
      (node (ref "13P-CN1") (pin "8") (pinfunction "8_8") (pintype "bidirectional"))
      (node (ref "R23") (pin "2") (pinfunction "2_2") (pintype "passive"))
    )
    (net (code "37") (name "Net-(C13-Pad2)") (class "Default")
      (node (ref "C13") (pin "2") (pinfunction "2_2") (pintype "passive"))
      (node (ref "R19") (pin "2") (pinfunction "2_2") (pintype "passive"))
    )
    (net (code "38") (name "Net-(D1-AK)") (class "Default")
      (node (ref "D1") (pin "3") (pinfunction "AK_3") (pintype "passive"))
      (node (ref "R22") (pin "2") (pinfunction "2_2") (pintype "passive"))
      (node (ref "U3") (pin "1") (pinfunction "OUT_1") (pintype "output"))
      (node (ref "U3") (pin "2") (pinfunction "IN-_2") (pintype "input"))
    )
    (net (code "39") (name "Net-(D2-AK)") (class "Default")
      (node (ref "D2") (pin "3") (pinfunction "AK_3") (pintype "passive"))
      (node (ref "R23") (pin "1") (pinfunction "1_1") (pintype "passive"))
      (node (ref "U3") (pin "6") (pinfunction "IN-_6") (pintype "input"))
      (node (ref "U3") (pin "7") (pinfunction "OUT_7") (pintype "output"))
    )
    (net (code "40") (name "Net-(H2-Pad8)") (class "Default")
      (node (ref "H2") (pin "8") (pinfunction "8_8") (pintype "passive"))
      (node (ref "JP2") (pin "2") (pinfunction "2_2") (pintype "passive"))
    )
    (net (code "41") (name "Net-(H3-Pad1)") (class "Default")
      (node (ref "H3") (pin "1") (pinfunction "1_1") (pintype "passive"))
      (node (ref "JP3") (pin "2") (pinfunction "2_2") (pintype "passive"))
    )
    (net (code "42") (name "Net-(H3-Pad8)") (class "Default")
      (node (ref "H3") (pin "8") (pinfunction "8_8") (pintype "passive"))
      (node (ref "JP1") (pin "2") (pinfunction "2_2") (pintype "passive"))
    )
    (net (code "43") (name "Net-(MIDI1-Pad4)") (class "Default")
      (node (ref "MIDI1") (pin "4") (pinfunction "4_4") (pintype "passive"))
      (node (ref "R30") (pin "2") (pinfunction "2_2") (pintype "passive"))
    )
    (net (code "44") (name "Net-(MIDI1-Pad5)") (class "Default")
      (node (ref "MIDI1") (pin "5") (pinfunction "5_5") (pintype "passive"))
      (node (ref "R31") (pin "2") (pinfunction "2_2") (pintype "passive"))
    )
    (net (code "45") (name "Net-(T1-B)") (class "Default")
      (node (ref "R32") (pin "2") (pinfunction "2_2") (pintype "passive"))
      (node (ref "T1") (pin "1") (pinfunction "B_1") (pintype "passive"))
    )
    (net (code "46") (name "Net-(T1-C)") (class "Default")
      (node (ref "R31") (pin "1") (pinfunction "1_1") (pintype "passive"))
      (node (ref "T1") (pin "3") (pinfunction "C_3") (pintype "passive"))
    )
    (net (code "47") (name "Net-(T2-B)") (class "Default")
      (node (ref "R34") (pin "2") (pinfunction "2_2") (pintype "passive"))
      (node (ref "T2") (pin "1") (pinfunction "B_1") (pintype "passive"))
    )
    (net (code "48") (name "Net-(T2-C)") (class "Default")
      (node (ref "R32") (pin "1") (pinfunction "1_1") (pintype "passive"))
      (node (ref "R33") (pin "1") (pinfunction "1_1") (pintype "passive"))
      (node (ref "T2") (pin "3") (pinfunction "C_3") (pintype "passive"))
    )
    (net (code "49") (name "Net-(U1A-IN+)") (class "Default")
      (node (ref "C3") (pin "1") (pinfunction "1_1") (pintype "passive"))
      (node (ref "H3") (pin "3") (pinfunction "3_3") (pintype "passive"))
      (node (ref "R1") (pin "2") (pinfunction "2_2") (pintype "passive"))
      (node (ref "U1") (pin "3") (pinfunction "IN+_3") (pintype "input"))
    )
    (net (code "50") (name "Net-(U1B-IN+)") (class "Default")
      (node (ref "C4") (pin "1") (pinfunction "1_1") (pintype "passive"))
      (node (ref "H3") (pin "4") (pinfunction "4_4") (pintype "passive"))
      (node (ref "R2") (pin "2") (pinfunction "2_2") (pintype "passive"))
      (node (ref "U1") (pin "5") (pinfunction "IN+_5") (pintype "input"))
    )
    (net (code "51") (name "Net-(U2A-IN+)") (class "Default")
      (node (ref "C5") (pin "1") (pinfunction "1_1") (pintype "passive"))
      (node (ref "H3") (pin "5") (pinfunction "5_5") (pintype "passive"))
      (node (ref "R3") (pin "2") (pinfunction "2_2") (pintype "passive"))
      (node (ref "U2") (pin "3") (pinfunction "IN+_3") (pintype "input"))
    )
    (net (code "52") (name "Net-(U2B-IN+)") (class "Default")
      (node (ref "C6") (pin "1") (pinfunction "1_1") (pintype "passive"))
      (node (ref "H3") (pin "6") (pinfunction "6_6") (pintype "passive"))
      (node (ref "R4") (pin "2") (pinfunction "2_2") (pintype "passive"))
      (node (ref "U2") (pin "5") (pinfunction "IN+_5") (pintype "input"))
    )
    (net (code "53") (name "Net-(U2C-IN+)") (class "Default")
      (node (ref "C7") (pin "1") (pinfunction "1_1") (pintype "passive"))
      (node (ref "H3") (pin "7") (pinfunction "7_7") (pintype "passive"))
      (node (ref "R5") (pin "2") (pinfunction "2_2") (pintype "passive"))
      (node (ref "U2") (pin "10") (pinfunction "IN+_10") (pintype "input"))
    )
    (net (code "54") (name "Net-(U3A-IN+)") (class "Default")
      (node (ref "C13") (pin "1") (pinfunction "1_1") (pintype "passive"))
      (node (ref "R21") (pin "1") (pinfunction "1_1") (pintype "passive"))
      (node (ref "TP3") (pin "TP") (pinfunction "TP_TP") (pintype "input"))
      (node (ref "U3") (pin "3") (pinfunction "IN+_3") (pintype "input"))
    )
    (net (code "55") (name "Net-(U3B-IN+)") (class "Default")
      (node (ref "C14") (pin "1") (pinfunction "1_1") (pintype "passive"))
      (node (ref "R20") (pin "2") (pinfunction "2_2") (pintype "passive"))
      (node (ref "TP2") (pin "TP") (pinfunction "TP_TP") (pintype "input"))
      (node (ref "U3") (pin "5") (pinfunction "IN+_5") (pintype "input"))
    )
    (net (code "56") (name "P1.0") (class "Default")
      (node (ref "C21") (pin "1") (pinfunction "1_1") (pintype "passive"))
      (node (ref "R26") (pin "2") (pinfunction "2_2") (pintype "passive"))
      (node (ref "R29") (pin "1") (pinfunction "1_1") (pintype "passive"))
      (node (ref "U6") (pin "31") (pinfunction "P1.0_31") (pintype "bidirectional"))
    )
    (net (code "57") (name "P1.1") (class "Default")
      (node (ref "H6") (pin "1") (pinfunction "1_1") (pintype "passive"))
      (node (ref "U6") (pin "1") (pinfunction "P1.1_1") (pintype "bidirectional"))
    )
    (net (code "58") (name "P1.2") (class "Default")
      (node (ref "R34") (pin "1") (pinfunction "1_1") (pintype "passive"))
      (node (ref "TP_SER") (pin "TP") (pinfunction "TP_TP") (pintype "input"))
      (node (ref "U6") (pin "2") (pinfunction "P1.2_2") (pintype "bidirectional"))
    )
    (net (code "59") (name "P1.3") (class "Default")
      (node (ref "C26") (pin "1") (pinfunction "1_1") (pintype "passive"))
      (node (ref "R37") (pin "1") (pinfunction "1_1") (pintype "passive"))
      (node (ref "R40") (pin "1") (pinfunction "1_1") (pintype "passive"))
      (node (ref "U6") (pin "3") (pinfunction "P1.3_3") (pintype "bidirectional"))
    )
    (net (code "60") (name "P1.4") (class "Default")
      (node (ref "C25") (pin "1") (pinfunction "1_1") (pintype "passive"))
      (node (ref "R36") (pin "1") (pinfunction "1_1") (pintype "passive"))
      (node (ref "R39") (pin "1") (pinfunction "1_1") (pintype "passive"))
      (node (ref "U6") (pin "4") (pinfunction "P1.4_4") (pintype "bidirectional"))
    )
    (net (code "61") (name "P1.5") (class "Default")
      (node (ref "C24") (pin "1") (pinfunction "1_1") (pintype "passive"))
      (node (ref "R35") (pin "1") (pinfunction "1_1") (pintype "passive"))
      (node (ref "R38") (pin "1") (pinfunction "1_1") (pintype "passive"))
      (node (ref "U6") (pin "5") (pinfunction "P1.5_5") (pintype "bidirectional"))
    )
    (net (code "62") (name "P1.6") (class "Default")
      (node (ref "C19") (pin "1") (pinfunction "1_1") (pintype "passive"))
      (node (ref "R24") (pin "2") (pinfunction "2_2") (pintype "passive"))
      (node (ref "R27") (pin "1") (pinfunction "1_1") (pintype "passive"))
      (node (ref "U6") (pin "21") (pinfunction "P1.6_21") (pintype "bidirectional"))
    )
    (net (code "63") (name "P1.7") (class "Default")
      (node (ref "C20") (pin "1") (pinfunction "1_1") (pintype "passive"))
      (node (ref "R25") (pin "2") (pinfunction "2_2") (pintype "passive"))
      (node (ref "R28") (pin "1") (pinfunction "1_1") (pintype "passive"))
      (node (ref "U6") (pin "22") (pinfunction "P1.7_22") (pintype "bidirectional"))
    )
    (net (code "64") (name "P2.3") (class "Default")
      (node (ref "H7") (pin "1") (pinfunction "1_1") (pintype "passive"))
      (node (ref "U6") (pin "15") (pinfunction "P2.3_15") (pintype "bidirectional"))
    )
    (net (code "65") (name "P2.4") (class "Default")
      (node (ref "H7") (pin "2") (pinfunction "2_2") (pintype "passive"))
      (node (ref "U6") (pin "16") (pinfunction "P2.4_16") (pintype "bidirectional"))
    )
    (net (code "66") (name "P2.5") (class "Default")
      (node (ref "H7") (pin "3") (pinfunction "3_3") (pintype "passive"))
      (node (ref "U6") (pin "17") (pinfunction "P2.5_17") (pintype "input"))
    )
    (net (code "67") (name "P2.6") (class "Default")
      (node (ref "C37") (pin "2") (pinfunction "2_2") (pintype "passive"))
      (node (ref "U6") (pin "26") (pinfunction "P2.6_26") (pintype "bidirectional"))
      (node (ref "X1") (pin "1") (pinfunction "1_1") (pintype "passive"))
    )
    (net (code "68") (name "P2.7") (class "Default")
      (node (ref "C36") (pin "2") (pinfunction "2_2") (pintype "passive"))
      (node (ref "U6") (pin "25") (pinfunction "P2.7_25") (pintype "bidirectional"))
      (node (ref "X1") (pin "2") (pinfunction "2_2") (pintype "passive"))
    )
    (net (code "69") (name "P3.0") (class "Default")
      (node (ref "H6") (pin "3") (pinfunction "3_3") (pintype "passive"))
      (node (ref "U6") (pin "7") (pinfunction "P3.0_7") (pintype "power_in"))
    )
    (net (code "70") (name "P3.1") (class "Default")
      (node (ref "H6") (pin "2") (pinfunction "2_2") (pintype "passive"))
      (node (ref "U6") (pin "6") (pinfunction "P3.1_6") (pintype "power_in"))
    )
    (net (code "71") (name "P3.2") (class "Default")
      (node (ref "H6") (pin "6") (pinfunction "6_6") (pintype "passive"))
      (node (ref "U6") (pin "12") (pinfunction "P3.2_12") (pintype "power_in"))
    )
    (net (code "72") (name "P3.3") (class "Default")
      (node (ref "H6") (pin "7") (pinfunction "7_7") (pintype "passive"))
      (node (ref "U6") (pin "13") (pinfunction "P3.3_13") (pintype "bidirectional"))
    )
    (net (code "73") (name "P3.4") (class "Default")
      (node (ref "H6") (pin "8") (pinfunction "8_8") (pintype "passive"))
      (node (ref "U6") (pin "14") (pinfunction "P3.4_14") (pintype "bidirectional"))
    )
    (net (code "74") (name "P3.5") (class "Default")
      (node (ref "H7") (pin "4") (pinfunction "4_4") (pintype "passive"))
      (node (ref "U6") (pin "18") (pinfunction "P3.5_18") (pintype "bidirectional"))
    )
    (net (code "75") (name "P3.6") (class "Default")
      (node (ref "H7") (pin "5") (pinfunction "5_5") (pintype "passive"))
      (node (ref "U6") (pin "19") (pinfunction "P3.6_19") (pintype "bidirectional"))
    )
    (net (code "76") (name "P3.7") (class "Default")
      (node (ref "H7") (pin "6") (pinfunction "6_6") (pintype "passive"))
      (node (ref "U6") (pin "20") (pinfunction "P3.7_20") (pintype "bidirectional"))
    )
    (net (code "77") (name "TEST") (class "Default")
      (node (ref "H8") (pin "1") (pinfunction "1_1") (pintype "passive"))
      (node (ref "U6") (pin "24") (pinfunction "TEST_24") (pintype "bidirectional"))
    )
    (net (code "78") (name "VIN") (class "Default")
      (node (ref "C1") (pin "+") (pinfunction "+_+") (pintype "passive"))
      (node (ref "C10") (pin "1") (pinfunction "1_1") (pintype "passive"))
      (node (ref "C11") (pin "1") (pinfunction "1_1") (pintype "passive"))
      (node (ref "C12") (pin "1") (pinfunction "1_1") (pintype "passive"))
      (node (ref "C9") (pin "1") (pinfunction "1_1") (pintype "passive"))
      (node (ref "FB1") (pin "2") (pinfunction "2_2") (pintype "bidirectional"))
      (node (ref "U1") (pin "8") (pinfunction "V+_8") (pintype "power_in"))
      (node (ref "U2") (pin "4") (pinfunction "V+_4") (pintype "power_in"))
    )
    (net (code "79") (name "unconnected-(13P-CN1-Pad9)") (class "Default")
      (node (ref "13P-CN1") (pin "9") (pinfunction "9_9") (pintype "bidirectional"))
    )
    (net (code "80") (name "unconnected-(MIDI1-Pad1)") (class "Default")
      (node (ref "MIDI1") (pin "1") (pinfunction "1_1") (pintype "passive"))
    )
    (net (code "81") (name "unconnected-(MIDI1-Pad3)") (class "Default")
      (node (ref "MIDI1") (pin "3") (pinfunction "3_3") (pintype "passive"))
    )
    (net (code "82") (name "unconnected-(U5-ADJ-Pad4)") (class "Default")
      (node (ref "U5") (pin "4") (pinfunction "ADJ_4") (pintype "passive"))
    )
    (net (code "83") (name "unconnected-(U6-NC_1-Pad8)") (class "Default")
      (node (ref "U6") (pin "8") (pinfunction "NC_1_8") (pintype "bidirectional"))
    )
    (net (code "84") (name "unconnected-(U6-NC_2-Pad32)") (class "Default")
      (node (ref "U6") (pin "32") (pinfunction "NC_2_32") (pintype "power_in"))
    )
    (net (code "85") (name "~{RST}") (class "Default")
      (node (ref "C35") (pin "1") (pinfunction "1_1") (pintype "passive"))
      (node (ref "H8") (pin "2") (pinfunction "2_2") (pintype "passive"))
      (node (ref "R41") (pin "2") (pinfunction "2_2") (pintype "passive"))
      (node (ref "U6") (pin "23") (pinfunction "RST_23") (pintype "bidirectional"))
    )
  )
)
